# ReferenceVoltage.net
KiCad netlist of a schematic drawn in Altium Designer
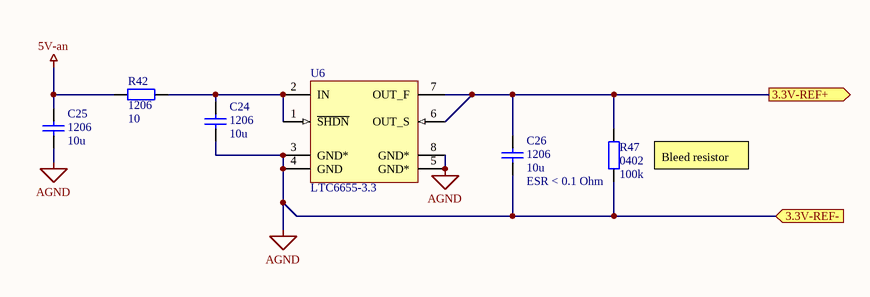
[diagram p0: ReferenceVoltage.SchDoc]

(export (version "E")
  (design (tool "Eeschema 10.0.6"))
  (components
    (comp (ref "C24")
      (value "1206")
      (footprint "SMD_Capacitor_1206")
      (description "Capacitor")
      (fields (field (name "ALTIUM_VALUE") "10u") (field (name "PUBLISHER") "Altium Limited"))
      (libsource (lib "Miscellaneous Devices") (part "Cap"))
    )
    (comp (ref "C25")
      (value "1206")
      (footprint "SMD_Capacitor_1206")
      (description "Capacitor")
      (fields (field (name "ALTIUM_VALUE") "10u") (field (name "PUBLISHER") "Altium Limited"))
      (libsource (lib "Miscellaneous Devices") (part "Cap"))
    )
    (comp (ref "C26")
      (value "1206")
      (footprint "SMD_Capacitor_1206")
      (description "Capacitor")
      (fields (field (name "ALTIUM_VALUE") "10u") (field (name "PUBLISHER") "Altium Limited"))
      (libsource (lib "Miscellaneous Devices") (part "Cap"))
    )
    (comp (ref "R42")
      (value "1206")
      (footprint "SMD_Resistor_1206")
      (description "Resistor")
      (fields (field (name "ALTIUM_VALUE") "10") (field (name "PUBLISHER") "Altium Limited"))
      (libsource (lib "Miscellaneous Devices") (part "Res2"))
    )
    (comp (ref "R47")
      (value "0402")
      (footprint "SMD_Resistor_0402")
      (description "Resistor")
      (fields (field (name "ALTIUM_VALUE") "100k") (field (name "PUBLISHER") "Altium Limited"))
      (libsource (lib "") (part "Res2_1"))
    )
    (comp (ref "U6")
      (value "LTC6655-3.3")
      (footprint "MSOP-8")
      (description "0.25ppm Noise, Low Drift  Precision References")
      (fields (field (name "PARTNUMBER") "LTC6655-2.5"))
      (libsource (lib "microcircuits_linear-voltage-regulator") (part "LTC6655-2.5"))
    )
  )
  (nets
    (net (code "1") (name "/3.3V-REF+") (class "Default")
      (node (ref "C26") (pin "2") (pinfunction "2_2") (pintype "passive"))
      (node (ref "R47") (pin "2") (pinfunction "2_2") (pintype "passive"))
      (node (ref "U6") (pin "6") (pinfunction "OUT_S_6") (pintype "input"))
      (node (ref "U6") (pin "7") (pinfunction "OUT_F_7") (pintype "power_in"))
    )
    (net (code "2") (name "5V-an") (class "Default")
      (node (ref "C25") (pin "2") (pinfunction "2_2") (pintype "passive"))
      (node (ref "R42") (pin "1") (pinfunction "1_1") (pintype "passive"))
    )
    (net (code "3") (name "AGND") (class "Default")
      (node (ref "C24") (pin "1") (pinfunction "1_1") (pintype "passive"))
      (node (ref "C25") (pin "1") (pinfunction "1_1") (pintype "passive"))
      (node (ref "C26") (pin "1") (pinfunction "1_1") (pintype "passive"))
      (node (ref "R47") (pin "1") (pinfunction "1_1") (pintype "passive"))
      (node (ref "U6") (pin "3") (pinfunction "GND*_3") (pintype "power_in"))
      (node (ref "U6") (pin "4") (pinfunction "GND_4") (pintype "power_in"))
      (node (ref "U6") (pin "5") (pinfunction "GND*_5") (pintype "power_in"))
      (node (ref "U6") (pin "8") (pinfunction "GND*_8") (pintype "power_in"))
    )
    (net (code "4") (name "Net-(U6-IN)") (class "Default")
      (node (ref "C24") (pin "2") (pinfunction "2_2") (pintype "passive"))
      (node (ref "R42") (pin "2") (pinfunction "2_2") (pintype "passive"))
      (node (ref "U6") (pin "1") (pinfunction "~{SHDN}_1") (pintype "input"))
      (node (ref "U6") (pin "2") (pinfunction "IN_2") (pintype "power_in"))
    )
  )
)
